# OpenLabKostkaSchemat.net
KiCad netlist of a schematic drawn in EAGLE
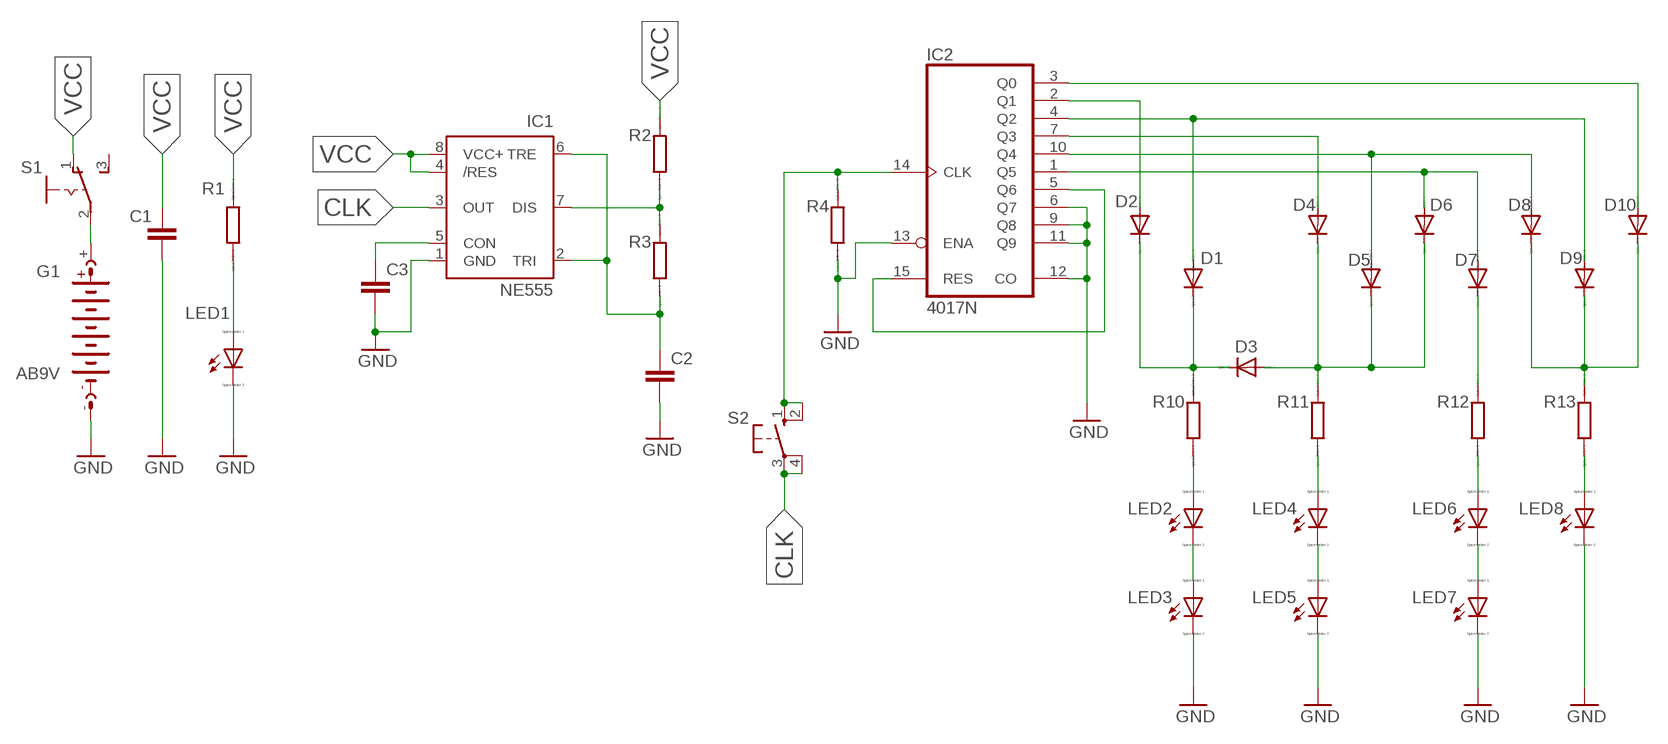
[diagram p0: schematic, sheet 1]

(export (version "E")
  (design (tool "Eeschema 10.0.6"))
  (components
    (comp (ref "C1")
      (value "C5/2.5")
      (footprint "eagle-import:C5B2.5")
      (libsource (lib "eagle-import") (part "C5/2.5"))
    )
    (comp (ref "C2")
      (value "C5/2.5")
      (footprint "eagle-import:C5B2.5")
      (libsource (lib "eagle-import") (part "C5/2.5"))
    )
    (comp (ref "C3")
      (value "C5/2.5")
      (footprint "eagle-import:C5B2.5")
      (libsource (lib "eagle-import") (part "C5/2.5"))
    )
    (comp (ref "D1")
      (value "1N4446")
      (footprint "eagle-import:DO35-10")
      (libsource (lib "eagle-import") (part "1N4446"))
    )
    (comp (ref "D2")
      (value "1N4446")
      (footprint "eagle-import:DO35-10")
      (libsource (lib "eagle-import") (part "1N4446"))
    )
    (comp (ref "D3")
      (value "1N4446")
      (footprint "eagle-import:DO35-10")
      (libsource (lib "eagle-import") (part "1N4446"))
    )
    (comp (ref "D4")
      (value "1N4446")
      (footprint "eagle-import:DO35-10")
      (libsource (lib "eagle-import") (part "1N4446"))
    )
    (comp (ref "D5")
      (value "1N4446")
      (footprint "eagle-import:DO35-10")
      (libsource (lib "eagle-import") (part "1N4446"))
    )
    (comp (ref "D6")
      (value "1N4446")
      (footprint "eagle-import:DO35-10")
      (libsource (lib "eagle-import") (part "1N4446"))
    )
    (comp (ref "D7")
      (value "1N4446")
      (footprint "eagle-import:DO35-10")
      (libsource (lib "eagle-import") (part "1N4446"))
    )
    (comp (ref "D8")
      (value "1N4446")
      (footprint "eagle-import:DO35-10")
      (libsource (lib "eagle-import") (part "1N4446"))
    )
    (comp (ref "D9")
      (value "1N4446")
      (footprint "eagle-import:DO35-10")
      (libsource (lib "eagle-import") (part "1N4446"))
    )
    (comp (ref "D10")
      (value "1N4446")
      (footprint "eagle-import:DO35-10")
      (libsource (lib "eagle-import") (part "1N4446"))
    )
    (comp (ref "G1")
      (value "AB9V")
      (footprint "eagle-import:AB9V")
      (libsource (lib "eagle-import") (part "AB9V"))
    )
    (comp (ref "IC1")
      (value "NE555")
      (footprint "eagle-import:DIL-08")
      (fields (field (name "MF") "Arrow Electronics") (field (name "MPN") "NE555N"))
      (libsource (lib "eagle-import") (part "NE555"))
    )
    (comp (ref "IC2")
      (value "4017N")
      (footprint "eagle-import:DIL16")
      (libsource (lib "eagle-import") (part "4017N"))
    )
    (comp (ref "LED1")
      (value "LED_ELD260")
      (footprint "eagle-import:LED_LD260")
      (libsource (lib "eagle-import") (part "LED_ELD260"))
    )
    (comp (ref "LED2")
      (value "LED_ELD260")
      (footprint "eagle-import:LED_LD260")
      (libsource (lib "eagle-import") (part "LED_ELD260"))
    )
    (comp (ref "LED3")
      (value "LED_ELD260")
      (footprint "eagle-import:LED_LD260")
      (libsource (lib "eagle-import") (part "LED_ELD260"))
    )
    (comp (ref "LED4")
      (value "LED_ELD260")
      (footprint "eagle-import:LED_LD260")
      (libsource (lib "eagle-import") (part "LED_ELD260"))
    )
    (comp (ref "LED5")
      (value "LED_ELD260")
      (footprint "eagle-import:LED_LD260")
      (libsource (lib "eagle-import") (part "LED_ELD260"))
    )
    (comp (ref "LED6")
      (value "LED_ELD260")
      (footprint "eagle-import:LED_LD260")
      (libsource (lib "eagle-import") (part "LED_ELD260"))
    )
    (comp (ref "LED7")
      (value "LED_ELD260")
      (footprint "eagle-import:LED_LD260")
      (libsource (lib "eagle-import") (part "LED_ELD260"))
    )
    (comp (ref "LED8")
      (value "LED_ELD260")
      (footprint "eagle-import:LED_LD260")
      (libsource (lib "eagle-import") (part "LED_ELD260"))
    )
    (comp (ref "R1")
      (value "R0204/7")
      (footprint "eagle-import:0204_7")
      (libsource (lib "eagle-import") (part "R0204/7"))
    )
    (comp (ref "R2")
      (value "R0204/7")
      (footprint "eagle-import:0204_7")
      (libsource (lib "eagle-import") (part "R0204/7"))
    )
    (comp (ref "R3")
      (value "R0204/7")
      (footprint "eagle-import:0204_7")
      (libsource (lib "eagle-import") (part "R0204/7"))
    )
    (comp (ref "R4")
      (value "R0204/7")
      (footprint "eagle-import:0204_7")
      (libsource (lib "eagle-import") (part "R0204/7"))
    )
    (comp (ref "R10")
      (value "R0204/7")
      (footprint "eagle-import:0204_7")
      (libsource (lib "eagle-import") (part "R0204/7"))
    )
    (comp (ref "R11")
      (value "R0204/7")
      (footprint "eagle-import:0204_7")
      (libsource (lib "eagle-import") (part "R0204/7"))
    )
    (comp (ref "R12")
      (value "R0204/7")
      (footprint "eagle-import:0204_7")
      (libsource (lib "eagle-import") (part "R0204/7"))
    )
    (comp (ref "R13")
      (value "R0204/7")
      (footprint "eagle-import:0204_7")
      (libsource (lib "eagle-import") (part "R0204/7"))
    )
    (comp (ref "S1")
      (value "255SB")
      (footprint "eagle-import:255SB")
      (libsource (lib "eagle-import") (part "255SB"))
    )
    (comp (ref "S2")
      (value "10-XX")
      (footprint "eagle-import:B3F-10XX")
      (fields (field (name "MPN") "B3F-1000"))
      (libsource (lib "eagle-import") (part "10-XX"))
    )
  )
  (nets
    (net (code "1") (name "CLK") (class "Default")
      (node (ref "IC1") (pin "3") (pinfunction "OUT_3") (pintype "output"))
      (node (ref "S2") (pin "3") (pinfunction "P_3") (pintype "passive"))
      (node (ref "S2") (pin "4") (pinfunction "P1_4") (pintype "passive"))
    )
    (net (code "2") (name "GND") (class "Default")
      (node (ref "C1") (pin "1") (pinfunction "1_1") (pintype "passive"))
      (node (ref "C2") (pin "2") (pinfunction "2_2") (pintype "passive"))
      (node (ref "C3") (pin "2") (pinfunction "2_2") (pintype "passive"))
      (node (ref "G1") (pin "-") (pinfunction "-_-") (pintype "passive"))
      (node (ref "IC1") (pin "1") (pinfunction "GND_1") (pintype "power_in"))
      (node (ref "IC2") (pin "11") (pinfunction "Q9_11") (pintype "output"))
      (node (ref "IC2") (pin "12") (pinfunction "CO_12") (pintype "output"))
      (node (ref "IC2") (pin "13") (pinfunction "ENA_13") (pintype "input"))
      (node (ref "IC2") (pin "6") (pinfunction "Q7_6") (pintype "output"))
      (node (ref "IC2") (pin "9") (pinfunction "Q8_9") (pintype "output"))
      (node (ref "LED1") (pin "K") (pinfunction "C_K") (pintype "passive"))
      (node (ref "LED3") (pin "K") (pinfunction "C_K") (pintype "passive"))
      (node (ref "LED5") (pin "K") (pinfunction "C_K") (pintype "passive"))
      (node (ref "LED7") (pin "K") (pinfunction "C_K") (pintype "passive"))
      (node (ref "LED8") (pin "K") (pinfunction "C_K") (pintype "passive"))
      (node (ref "R4") (pin "1") (pinfunction "1_1") (pintype "passive"))
    )
    (net (code "3") (name "Net-(D1-PadC)") (class "Default")
      (node (ref "D1") (pin "C") (pinfunction "C_C") (pintype "passive"))
      (node (ref "D2") (pin "C") (pinfunction "C_C") (pintype "passive"))
      (node (ref "D3") (pin "C") (pinfunction "C_C") (pintype "passive"))
      (node (ref "R10") (pin "2") (pinfunction "2_2") (pintype "passive"))
    )
    (net (code "4") (name "Net-(D3-PadA)") (class "Default")
      (node (ref "D3") (pin "A") (pinfunction "A_A") (pintype "passive"))
      (node (ref "D4") (pin "C") (pinfunction "C_C") (pintype "passive"))
      (node (ref "D5") (pin "C") (pinfunction "C_C") (pintype "passive"))
      (node (ref "D6") (pin "C") (pinfunction "C_C") (pintype "passive"))
      (node (ref "R11") (pin "2") (pinfunction "2_2") (pintype "passive"))
    )
    (net (code "5") (name "Net-(D7-PadC)") (class "Default")
      (node (ref "D7") (pin "C") (pinfunction "C_C") (pintype "passive"))
      (node (ref "R12") (pin "2") (pinfunction "2_2") (pintype "passive"))
    )
    (net (code "6") (name "Net-(D10-PadC)") (class "Default")
      (node (ref "D10") (pin "C") (pinfunction "C_C") (pintype "passive"))
      (node (ref "D8") (pin "C") (pinfunction "C_C") (pintype "passive"))
      (node (ref "D9") (pin "C") (pinfunction "C_C") (pintype "passive"))
      (node (ref "R13") (pin "2") (pinfunction "2_2") (pintype "passive"))
    )
    (net (code "7") (name "Net-(IC1-CON)") (class "Default")
      (node (ref "C3") (pin "1") (pinfunction "1_1") (pintype "passive"))
      (node (ref "IC1") (pin "5") (pinfunction "CON_5") (pintype "input"))
    )
    (net (code "8") (name "Net-(IC1-DIS)") (class "Default")
      (node (ref "IC1") (pin "7") (pinfunction "DIS_7") (pintype "input"))
      (node (ref "R2") (pin "1") (pinfunction "1_1") (pintype "passive"))
      (node (ref "R3") (pin "2") (pinfunction "2_2") (pintype "passive"))
    )
    (net (code "9") (name "Net-(IC1-TRE)") (class "Default")
      (node (ref "C2") (pin "1") (pinfunction "1_1") (pintype "passive"))
      (node (ref "IC1") (pin "2") (pinfunction "TRI_2") (pintype "input"))
      (node (ref "IC1") (pin "6") (pinfunction "TRE_6") (pintype "input"))
      (node (ref "R3") (pin "1") (pinfunction "1_1") (pintype "passive"))
    )
    (net (code "10") (name "Net-(IC2A-CLK)") (class "Default")
      (node (ref "IC2") (pin "14") (pinfunction "CLK_14") (pintype "input"))
      (node (ref "R4") (pin "2") (pinfunction "2_2") (pintype "passive"))
      (node (ref "S2") (pin "1") (pinfunction "S_1") (pintype "passive"))
      (node (ref "S2") (pin "2") (pinfunction "S1_2") (pintype "passive"))
    )
    (net (code "11") (name "Net-(IC2A-Q0)") (class "Default")
      (node (ref "D10") (pin "A") (pinfunction "A_A") (pintype "passive"))
      (node (ref "IC2") (pin "3") (pinfunction "Q0_3") (pintype "output"))
    )
    (net (code "12") (name "Net-(IC2A-Q1)") (class "Default")
      (node (ref "D2") (pin "A") (pinfunction "A_A") (pintype "passive"))
      (node (ref "IC2") (pin "2") (pinfunction "Q1_2") (pintype "output"))
    )
    (net (code "13") (name "Net-(IC2A-Q2)") (class "Default")
      (node (ref "D1") (pin "A") (pinfunction "A_A") (pintype "passive"))
      (node (ref "D9") (pin "A") (pinfunction "A_A") (pintype "passive"))
      (node (ref "IC2") (pin "4") (pinfunction "Q2_4") (pintype "output"))
    )
    (net (code "14") (name "Net-(IC2A-Q3)") (class "Default")
      (node (ref "D4") (pin "A") (pinfunction "A_A") (pintype "passive"))
      (node (ref "IC2") (pin "7") (pinfunction "Q3_7") (pintype "output"))
    )
    (net (code "15") (name "Net-(IC2A-Q4)") (class "Default")
      (node (ref "D5") (pin "A") (pinfunction "A_A") (pintype "passive"))
      (node (ref "D8") (pin "A") (pinfunction "A_A") (pintype "passive"))
      (node (ref "IC2") (pin "10") (pinfunction "Q4_10") (pintype "output"))
    )
    (net (code "16") (name "Net-(IC2A-Q5)") (class "Default")
      (node (ref "D6") (pin "A") (pinfunction "A_A") (pintype "passive"))
      (node (ref "D7") (pin "A") (pinfunction "A_A") (pintype "passive"))
      (node (ref "IC2") (pin "1") (pinfunction "Q5_1") (pintype "output"))
    )
    (net (code "17") (name "Net-(IC2A-Q6)") (class "Default")
      (node (ref "IC2") (pin "15") (pinfunction "RES_15") (pintype "input"))
      (node (ref "IC2") (pin "5") (pinfunction "Q6_5") (pintype "output"))
    )
    (net (code "18") (name "Net-(LED1-PadA)") (class "Default")
      (node (ref "LED1") (pin "A") (pinfunction "A_A") (pintype "passive"))
      (node (ref "R1") (pin "1") (pinfunction "1_1") (pintype "passive"))
    )
    (net (code "19") (name "Net-(LED2-C)") (class "Default")
      (node (ref "LED2") (pin "K") (pinfunction "C_K") (pintype "passive"))
      (node (ref "LED3") (pin "A") (pinfunction "A_A") (pintype "passive"))
    )
    (net (code "20") (name "Net-(LED2-PadA)") (class "Default")
      (node (ref "LED2") (pin "A") (pinfunction "A_A") (pintype "passive"))
      (node (ref "R10") (pin "1") (pinfunction "1_1") (pintype "passive"))
    )
    (net (code "21") (name "Net-(LED4-C)") (class "Default")
      (node (ref "LED4") (pin "K") (pinfunction "C_K") (pintype "passive"))
      (node (ref "LED5") (pin "A") (pinfunction "A_A") (pintype "passive"))
    )
    (net (code "22") (name "Net-(LED4-PadA)") (class "Default")
      (node (ref "LED4") (pin "A") (pinfunction "A_A") (pintype "passive"))
      (node (ref "R11") (pin "1") (pinfunction "1_1") (pintype "passive"))
    )
    (net (code "23") (name "Net-(LED6-C)") (class "Default")
      (node (ref "LED6") (pin "K") (pinfunction "C_K") (pintype "passive"))
      (node (ref "LED7") (pin "A") (pinfunction "A_A") (pintype "passive"))
    )
    (net (code "24") (name "Net-(LED6-PadA)") (class "Default")
      (node (ref "LED6") (pin "A") (pinfunction "A_A") (pintype "passive"))
      (node (ref "R12") (pin "1") (pinfunction "1_1") (pintype "passive"))
    )
    (net (code "25") (name "Net-(LED8-PadA)") (class "Default")
      (node (ref "LED8") (pin "A") (pinfunction "A_A") (pintype "passive"))
      (node (ref "R13") (pin "1") (pinfunction "1_1") (pintype "passive"))
    )
    (net (code "26") (name "Net-(S1-P)") (class "Default")
      (node (ref "G1") (pin "+") (pinfunction "+_+") (pintype "passive"))
      (node (ref "S1") (pin "2") (pinfunction "P_2") (pintype "passive"))
    )
    (net (code "27") (name "VCC") (class "Default")
      (node (ref "C1") (pin "2") (pinfunction "2_2") (pintype "passive"))
      (node (ref "IC1") (pin "4") (pinfunction "/RES_4") (pintype "input"))
      (node (ref "IC1") (pin "8") (pinfunction "VCC+_8") (pintype "power_in"))
      (node (ref "R1") (pin "2") (pinfunction "2_2") (pintype "passive"))
      (node (ref "R2") (pin "2") (pinfunction "2_2") (pintype "passive"))
      (node (ref "S1") (pin "1") (pinfunction "O_1") (pintype "passive"))
    )
    (net (code "28") (name "unconnected-(S1-S-Pad3)") (class "Default")
      (node (ref "S1") (pin "3") (pinfunction "S_3") (pintype "passive"))
    )
  )
)
